# tipController.net
KiCad netlist of a schematic drawn in Altium Designer
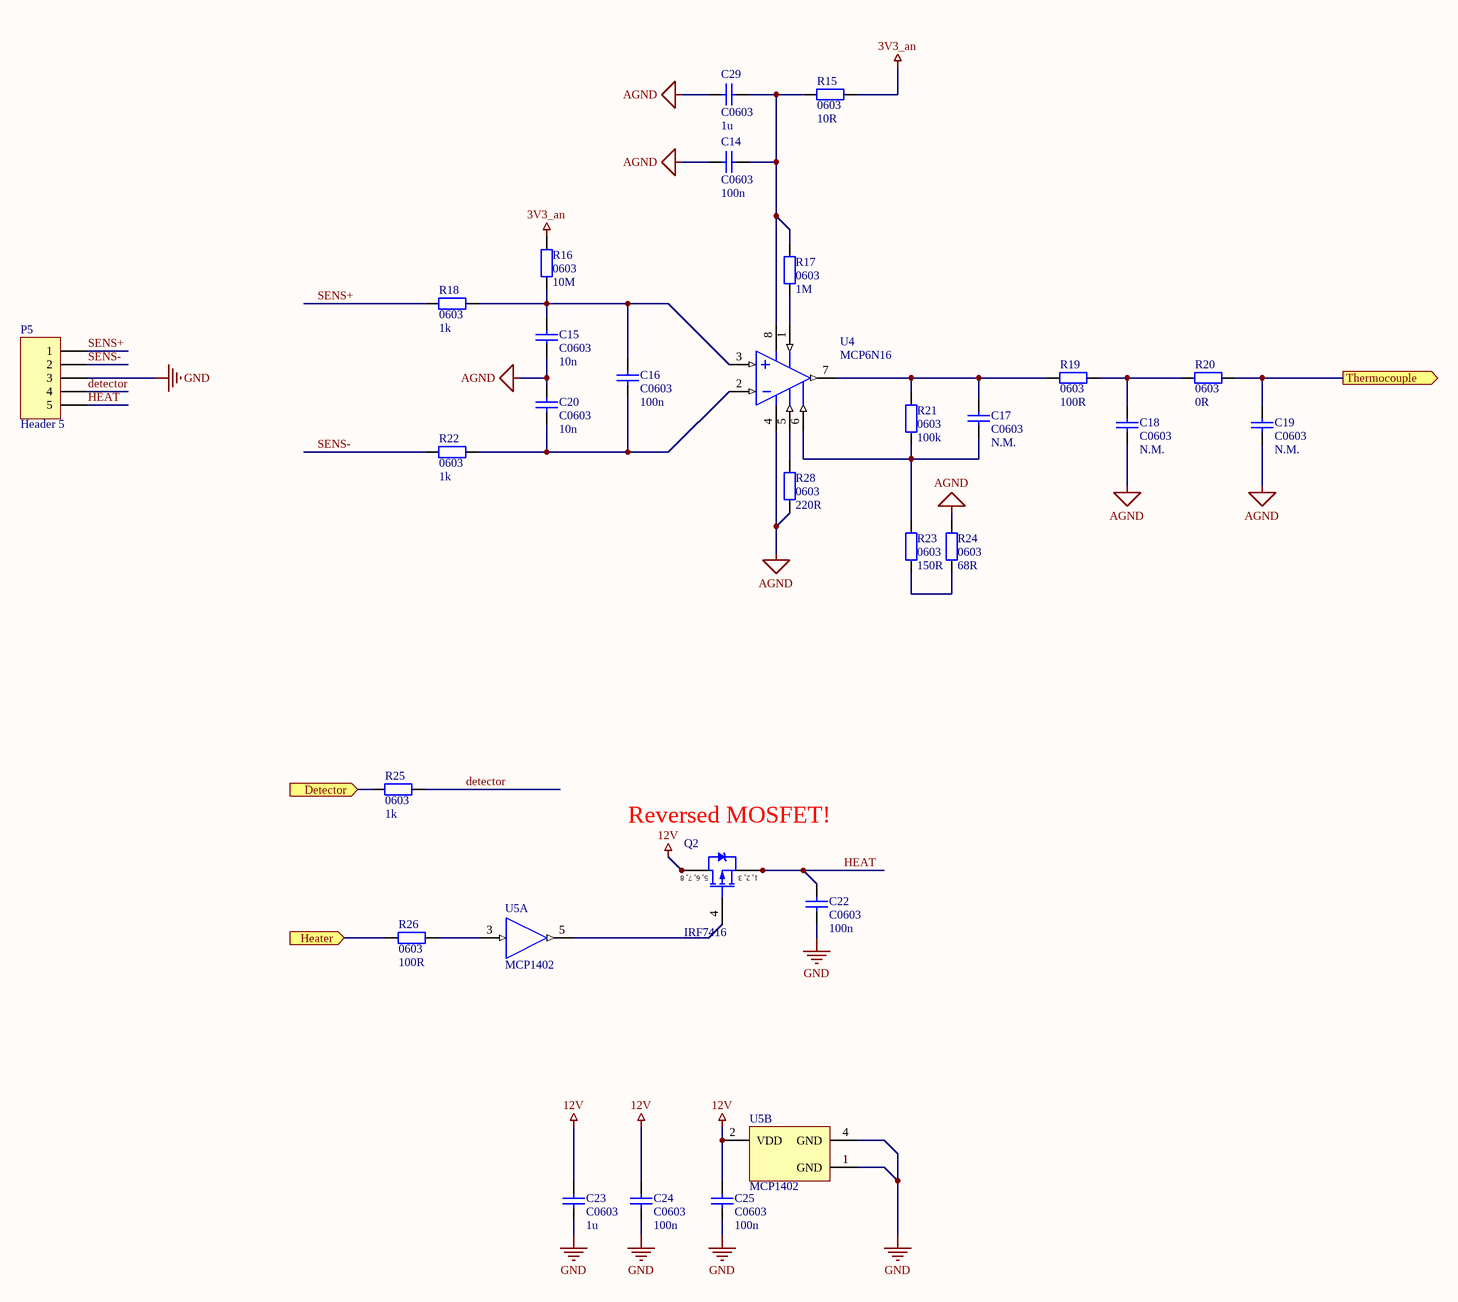
[diagram p0: tipController.SchDoc]

(export (version "E")
  (design (tool "Eeschema 10.0.6"))
  (components
    (comp (ref "C14")
      (value "100n")
      (footprint "C0603")
      (description "Generic capacitor")
      (libsource (lib "_RLC") (part "Cap"))
    )
    (comp (ref "C15")
      (value "10n")
      (footprint "C0603")
      (description "Generic capacitor")
      (libsource (lib "_RLC") (part "Cap"))
    )
    (comp (ref "C16")
      (value "100n")
      (footprint "C0603")
      (description "Generic capacitor")
      (libsource (lib "_RLC") (part "Cap"))
    )
    (comp (ref "C17")
      (value "N.M.")
      (footprint "C0603")
      (description "Generic capacitor")
      (libsource (lib "_RLC") (part "Cap"))
    )
    (comp (ref "C18")
      (value "N.M.")
      (footprint "C0603")
      (description "Generic capacitor")
      (libsource (lib "_RLC") (part "Cap"))
    )
    (comp (ref "C19")
      (value "N.M.")
      (footprint "C0603")
      (description "Generic capacitor")
      (libsource (lib "_RLC") (part "Cap"))
    )
    (comp (ref "C20")
      (value "10n")
      (footprint "C0603")
      (description "Generic capacitor")
      (libsource (lib "_RLC") (part "Cap"))
    )
    (comp (ref "C22")
      (value "100n")
      (footprint "C0603")
      (description "Generic capacitor")
      (libsource (lib "_RLC") (part "Cap"))
    )
    (comp (ref "C23")
      (value "1u")
      (footprint "C0603")
      (description "Generic capacitor")
      (libsource (lib "_RLC") (part "Cap"))
    )
    (comp (ref "C24")
      (value "100n")
      (footprint "C0603")
      (description "Generic capacitor")
      (libsource (lib "_RLC") (part "Cap"))
    )
    (comp (ref "C25")
      (value "100n")
      (footprint "C0603")
      (description "Generic capacitor")
      (libsource (lib "_RLC") (part "Cap"))
    )
    (comp (ref "C29")
      (value "1u")
      (footprint "C0603")
      (description "Generic capacitor")
      (libsource (lib "_RLC") (part "Cap"))
    )
    (comp (ref "P5")
      (value "Header 5")
      (footprint "HDR1X5")
      (description "Header, 5-Pin")
      (fields (field (name "PUBLISHER") "Altium Limited"))
      (libsource (lib "_Connectors") (part "Header 5"))
    )
    (comp (ref "Q2")
      (value "IRF7416")
      (footprint "SOIC-8_M")
      (description "Power P-MOSFET")
      (fields (field (name "PUBLISHER") "Altium Limited"))
      (libsource (lib "_Transistors") (part "IRF7416"))
    )
    (comp (ref "R15")
      (value "10R")
      (footprint "0603")
      (description "Generic resistor")
      (libsource (lib "") (part "Res_3"))
    )
    (comp (ref "R16")
      (value "10M")
      (footprint "0603")
      (description "Generic resistor")
      (libsource (lib "") (part "Res_2"))
    )
    (comp (ref "R17")
      (value "1M")
      (footprint "0603")
      (description "Generic resistor")
      (libsource (lib "") (part "Res_2"))
    )
    (comp (ref "R18")
      (value "1k")
      (footprint "0603")
      (description "Generic resistor")
      (libsource (lib "") (part "Res_1"))
    )
    (comp (ref "R19")
      (value "100R")
      (footprint "0603")
      (description "Generic resistor")
      (libsource (lib "") (part "Res_1"))
    )
    (comp (ref "R20")
      (value "0R")
      (footprint "0603")
      (description "Generic resistor")
      (libsource (lib "") (part "Res_1"))
    )
    (comp (ref "R21")
      (value "100k")
      (footprint "0603")
      (description "Generic resistor")
      (libsource (lib "") (part "Res_2"))
    )
    (comp (ref "R22")
      (value "1k")
      (footprint "0603")
      (description "Generic resistor")
      (libsource (lib "") (part "Res_1"))
    )
    (comp (ref "R23")
      (value "150R")
      (footprint "0603")
      (description "Generic resistor")
      (libsource (lib "") (part "Res_2"))
    )
    (comp (ref "R24")
      (value "68R")
      (footprint "0603")
      (description "Generic resistor")
      (libsource (lib "_RLC") (part "Res"))
    )
    (comp (ref "R25")
      (value "1k")
      (footprint "0603")
      (description "Generic resistor")
      (libsource (lib "") (part "Res_1"))
    )
    (comp (ref "R26")
      (value "100R")
      (footprint "0603")
      (description "Generic resistor")
      (libsource (lib "") (part "Res_1"))
    )
    (comp (ref "R28")
      (value "220R")
      (footprint "0603")
      (description "Generic resistor")
      (libsource (lib "") (part "Res_2"))
    )
    (comp (ref "U4")
      (value "MCP6N16")
      (footprint "MSOP-MS8_M")
      (libsource (lib "_Microcircuits") (part "MCP6N16"))
    )
    (comp (ref "U5")
      (value "MCP1402")
      (footprint "SOT23-5_M")
      (description "MCP1402 MOSFET driver")
      (libsource (lib "_Microcircuits") (part "MCP1402"))
    )
  )
  (nets
    (net (code "1") (name "/Detector") (class "Default")
      (node (ref "R25") (pin "1") (pinfunction "1_1") (pintype "passive"))
    )
    (net (code "2") (name "/HEAT") (class "Default")
      (node (ref "C22") (pin "1") (pinfunction "1_1") (pintype "passive"))
      (node (ref "P5") (pin "5") (pinfunction "5_5") (pintype "passive"))
      (node (ref "Q2") (pin "1") (pinfunction "S_1") (pintype "passive"))
      (node (ref "Q2") (pin "2") (pinfunction "S_2") (pintype "passive"))
      (node (ref "Q2") (pin "3") (pinfunction "S_3") (pintype "passive"))
    )
    (net (code "3") (name "/Heater") (class "Default")
      (node (ref "R26") (pin "1") (pinfunction "1_1") (pintype "passive"))
    )
    (net (code "4") (name "/SENS+") (class "Default")
      (node (ref "P5") (pin "1") (pinfunction "1_1") (pintype "passive"))
      (node (ref "R18") (pin "1") (pinfunction "1_1") (pintype "passive"))
    )
    (net (code "5") (name "/SENS-") (class "Default")
      (node (ref "P5") (pin "2") (pinfunction "2_2") (pintype "passive"))
      (node (ref "R22") (pin "1") (pinfunction "1_1") (pintype "passive"))
    )
    (net (code "6") (name "/Thermocouple") (class "Default")
      (node (ref "C19") (pin "1") (pinfunction "1_1") (pintype "passive"))
      (node (ref "R20") (pin "2") (pinfunction "2_2") (pintype "passive"))
    )
    (net (code "7") (name "/detector") (class "Default")
      (node (ref "P5") (pin "4") (pinfunction "4_4") (pintype "passive"))
      (node (ref "R25") (pin "2") (pinfunction "2_2") (pintype "passive"))
    )
    (net (code "8") (name "3V3_an") (class "Default")
      (node (ref "R15") (pin "1") (pinfunction "1_1") (pintype "passive"))
      (node (ref "R16") (pin "1") (pinfunction "1_1") (pintype "passive"))
    )
    (net (code "9") (name "12V") (class "Default")
      (node (ref "C23") (pin "1") (pinfunction "1_1") (pintype "passive"))
      (node (ref "C24") (pin "1") (pinfunction "1_1") (pintype "passive"))
      (node (ref "C25") (pin "1") (pinfunction "1_1") (pintype "passive"))
      (node (ref "Q2") (pin "5") (pinfunction "D_5") (pintype "passive"))
      (node (ref "Q2") (pin "6") (pinfunction "D_6") (pintype "passive"))
      (node (ref "Q2") (pin "7") (pinfunction "D_7") (pintype "passive"))
      (node (ref "Q2") (pin "8") (pinfunction "D_8") (pintype "passive"))
      (node (ref "U5") (pin "2") (pinfunction "VDD_2") (pintype "power_in"))
    )
    (net (code "10") (name "AGND") (class "Default")
      (node (ref "C14") (pin "1") (pinfunction "1_1") (pintype "passive"))
      (node (ref "C15") (pin "1") (pinfunction "1_1") (pintype "passive"))
      (node (ref "C18") (pin "2") (pinfunction "2_2") (pintype "passive"))
      (node (ref "C19") (pin "2") (pinfunction "2_2") (pintype "passive"))
      (node (ref "C20") (pin "1") (pinfunction "1_1") (pintype "passive"))
      (node (ref "C29") (pin "2") (pinfunction "2_2") (pintype "passive"))
      (node (ref "R24") (pin "2") (pinfunction "2_2") (pintype "passive"))
      (node (ref "R28") (pin "2") (pinfunction "2_2") (pintype "passive"))
      (node (ref "U4") (pin "4") (pinfunction "VSS_4") (pintype "power_in"))
    )
    (net (code "11") (name "GND") (class "Default")
      (node (ref "C22") (pin "2") (pinfunction "2_2") (pintype "passive"))
      (node (ref "C23") (pin "2") (pinfunction "2_2") (pintype "passive"))
      (node (ref "C24") (pin "2") (pinfunction "2_2") (pintype "passive"))
      (node (ref "C25") (pin "2") (pinfunction "2_2") (pintype "passive"))
      (node (ref "P5") (pin "3") (pinfunction "3_3") (pintype "passive"))
      (node (ref "U5") (pin "1") (pinfunction "GND_1") (pintype "power_in"))
      (node (ref "U5") (pin "4") (pinfunction "GND_4") (pintype "power_in"))
    )
    (net (code "12") (name "Net-(C18-Pad1)") (class "Default")
      (node (ref "C18") (pin "1") (pinfunction "1_1") (pintype "passive"))
      (node (ref "R19") (pin "2") (pinfunction "2_2") (pintype "passive"))
      (node (ref "R20") (pin "1") (pinfunction "1_1") (pintype "passive"))
    )
    (net (code "13") (name "Net-(Q2-G)") (class "Default")
      (node (ref "Q2") (pin "4") (pinfunction "G_4") (pintype "passive"))
      (node (ref "U5") (pin "5") (pinfunction "OUT_5") (pintype "output"))
    )
    (net (code "14") (name "Net-(R23-Pad2)") (class "Default")
      (node (ref "R23") (pin "2") (pinfunction "2_2") (pintype "passive"))
      (node (ref "R24") (pin "1") (pinfunction "1_1") (pintype "passive"))
    )
    (net (code "15") (name "Net-(U4-EN)") (class "Default")
      (node (ref "R17") (pin "2") (pinfunction "2_2") (pintype "passive"))
      (node (ref "U4") (pin "1") (pinfunction "EN_1") (pintype "input"))
    )
    (net (code "16") (name "Net-(U4-FB)") (class "Default")
      (node (ref "C17") (pin "2") (pinfunction "2_2") (pintype "passive"))
      (node (ref "R21") (pin "2") (pinfunction "2_2") (pintype "passive"))
      (node (ref "R23") (pin "1") (pinfunction "1_1") (pintype "passive"))
      (node (ref "U4") (pin "6") (pinfunction "FB_6") (pintype "input"))
    )
    (net (code "17") (name "Net-(U4-VDD)") (class "Default")
      (node (ref "C14") (pin "2") (pinfunction "2_2") (pintype "passive"))
      (node (ref "C29") (pin "1") (pinfunction "1_1") (pintype "passive"))
      (node (ref "R15") (pin "2") (pinfunction "2_2") (pintype "passive"))
      (node (ref "R17") (pin "1") (pinfunction "1_1") (pintype "passive"))
      (node (ref "U4") (pin "8") (pinfunction "VDD_8") (pintype "power_in"))
    )
    (net (code "18") (name "Net-(U4-VIN+)") (class "Default")
      (node (ref "C15") (pin "2") (pinfunction "2_2") (pintype "passive"))
      (node (ref "C16") (pin "1") (pinfunction "1_1") (pintype "passive"))
      (node (ref "R16") (pin "2") (pinfunction "2_2") (pintype "passive"))
      (node (ref "R18") (pin "2") (pinfunction "2_2") (pintype "passive"))
      (node (ref "U4") (pin "3") (pinfunction "VIN+_3") (pintype "input"))
    )
    (net (code "19") (name "Net-(U4-VIN-)") (class "Default")
      (node (ref "C16") (pin "2") (pinfunction "2_2") (pintype "passive"))
      (node (ref "C20") (pin "2") (pinfunction "2_2") (pintype "passive"))
      (node (ref "R22") (pin "2") (pinfunction "2_2") (pintype "passive"))
      (node (ref "U4") (pin "2") (pinfunction "VIN-_2") (pintype "input"))
    )
    (net (code "20") (name "Net-(U4-VOUT)") (class "Default")
      (node (ref "C17") (pin "1") (pinfunction "1_1") (pintype "passive"))
      (node (ref "R19") (pin "1") (pinfunction "1_1") (pintype "passive"))
      (node (ref "R21") (pin "1") (pinfunction "1_1") (pintype "passive"))
      (node (ref "U4") (pin "7") (pinfunction "VOUT_7") (pintype "output"))
    )
    (net (code "21") (name "Net-(U4-Vref)") (class "Default")
      (node (ref "R28") (pin "1") (pinfunction "1_1") (pintype "passive"))
      (node (ref "U4") (pin "5") (pinfunction "Vref_5") (pintype "input"))
    )
    (net (code "22") (name "Net-(U5A-IN)") (class "Default")
      (node (ref "R26") (pin "2") (pinfunction "2_2") (pintype "passive"))
      (node (ref "U5") (pin "3") (pinfunction "IN_3") (pintype "input"))
    )
  )
)
